# SCH_sensors_2026-05-06.net
KiCad netlist of a schematic drawn in EasyEDA
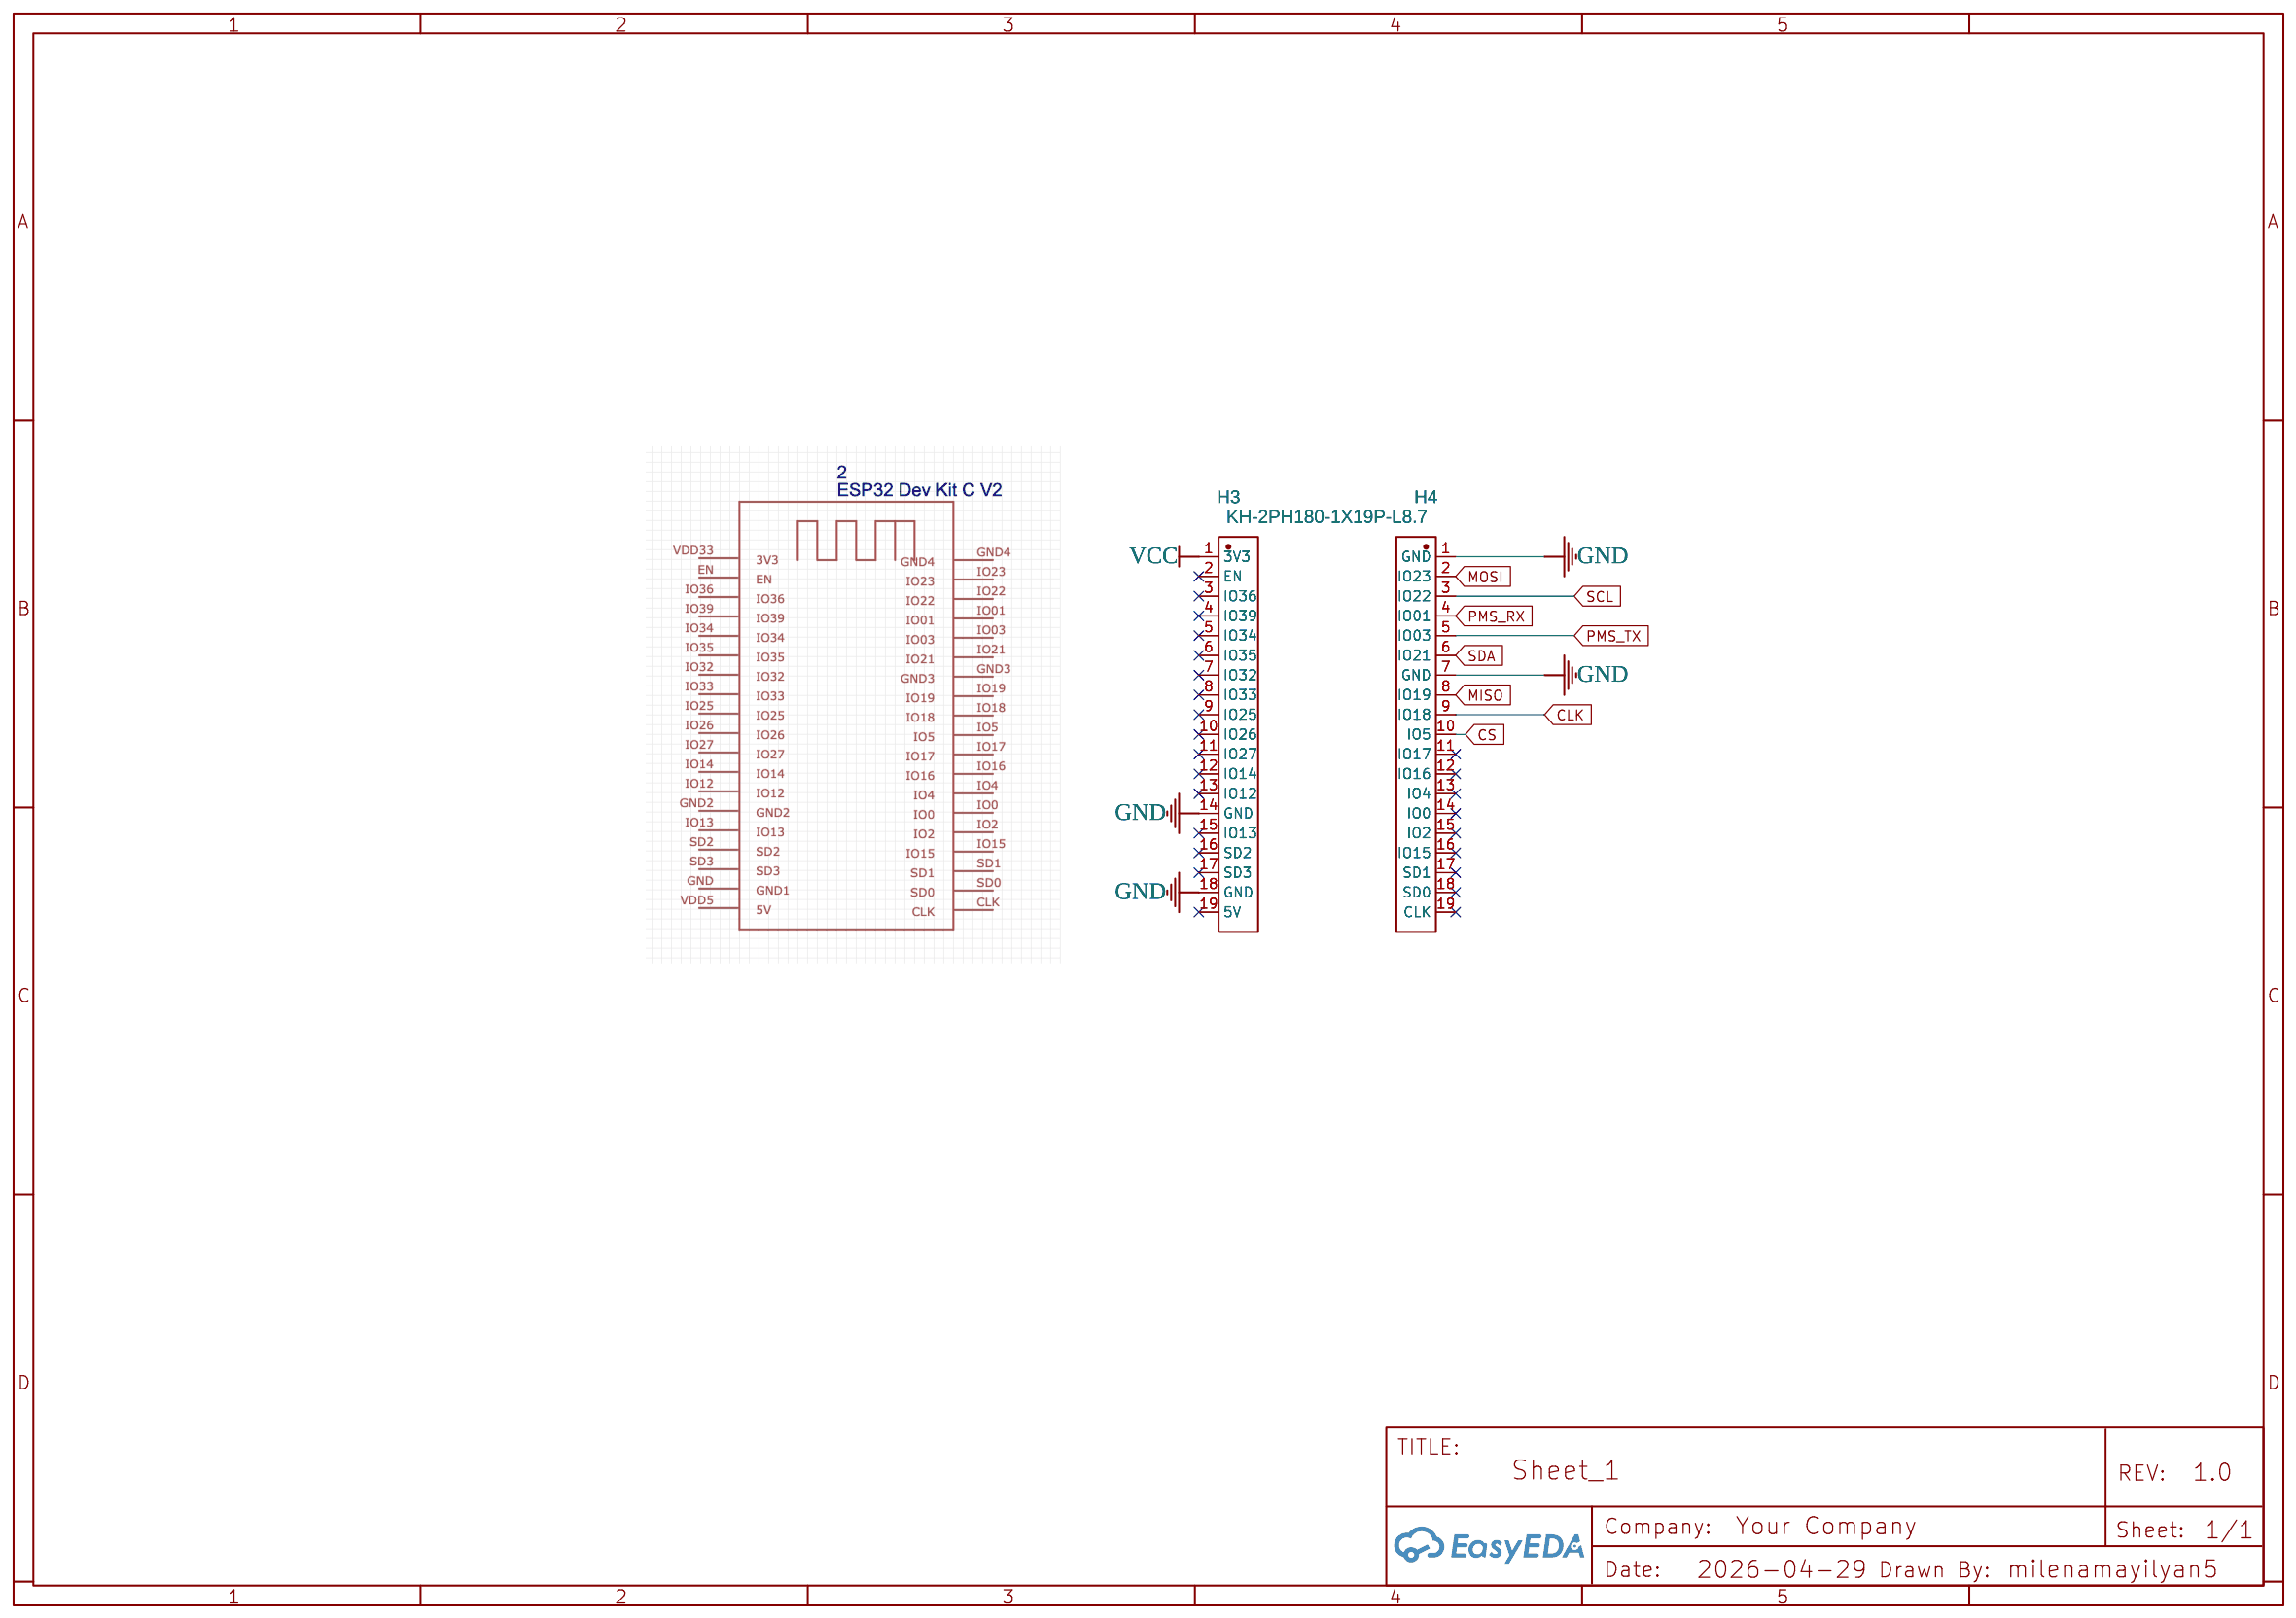
[diagram p0: esp32]
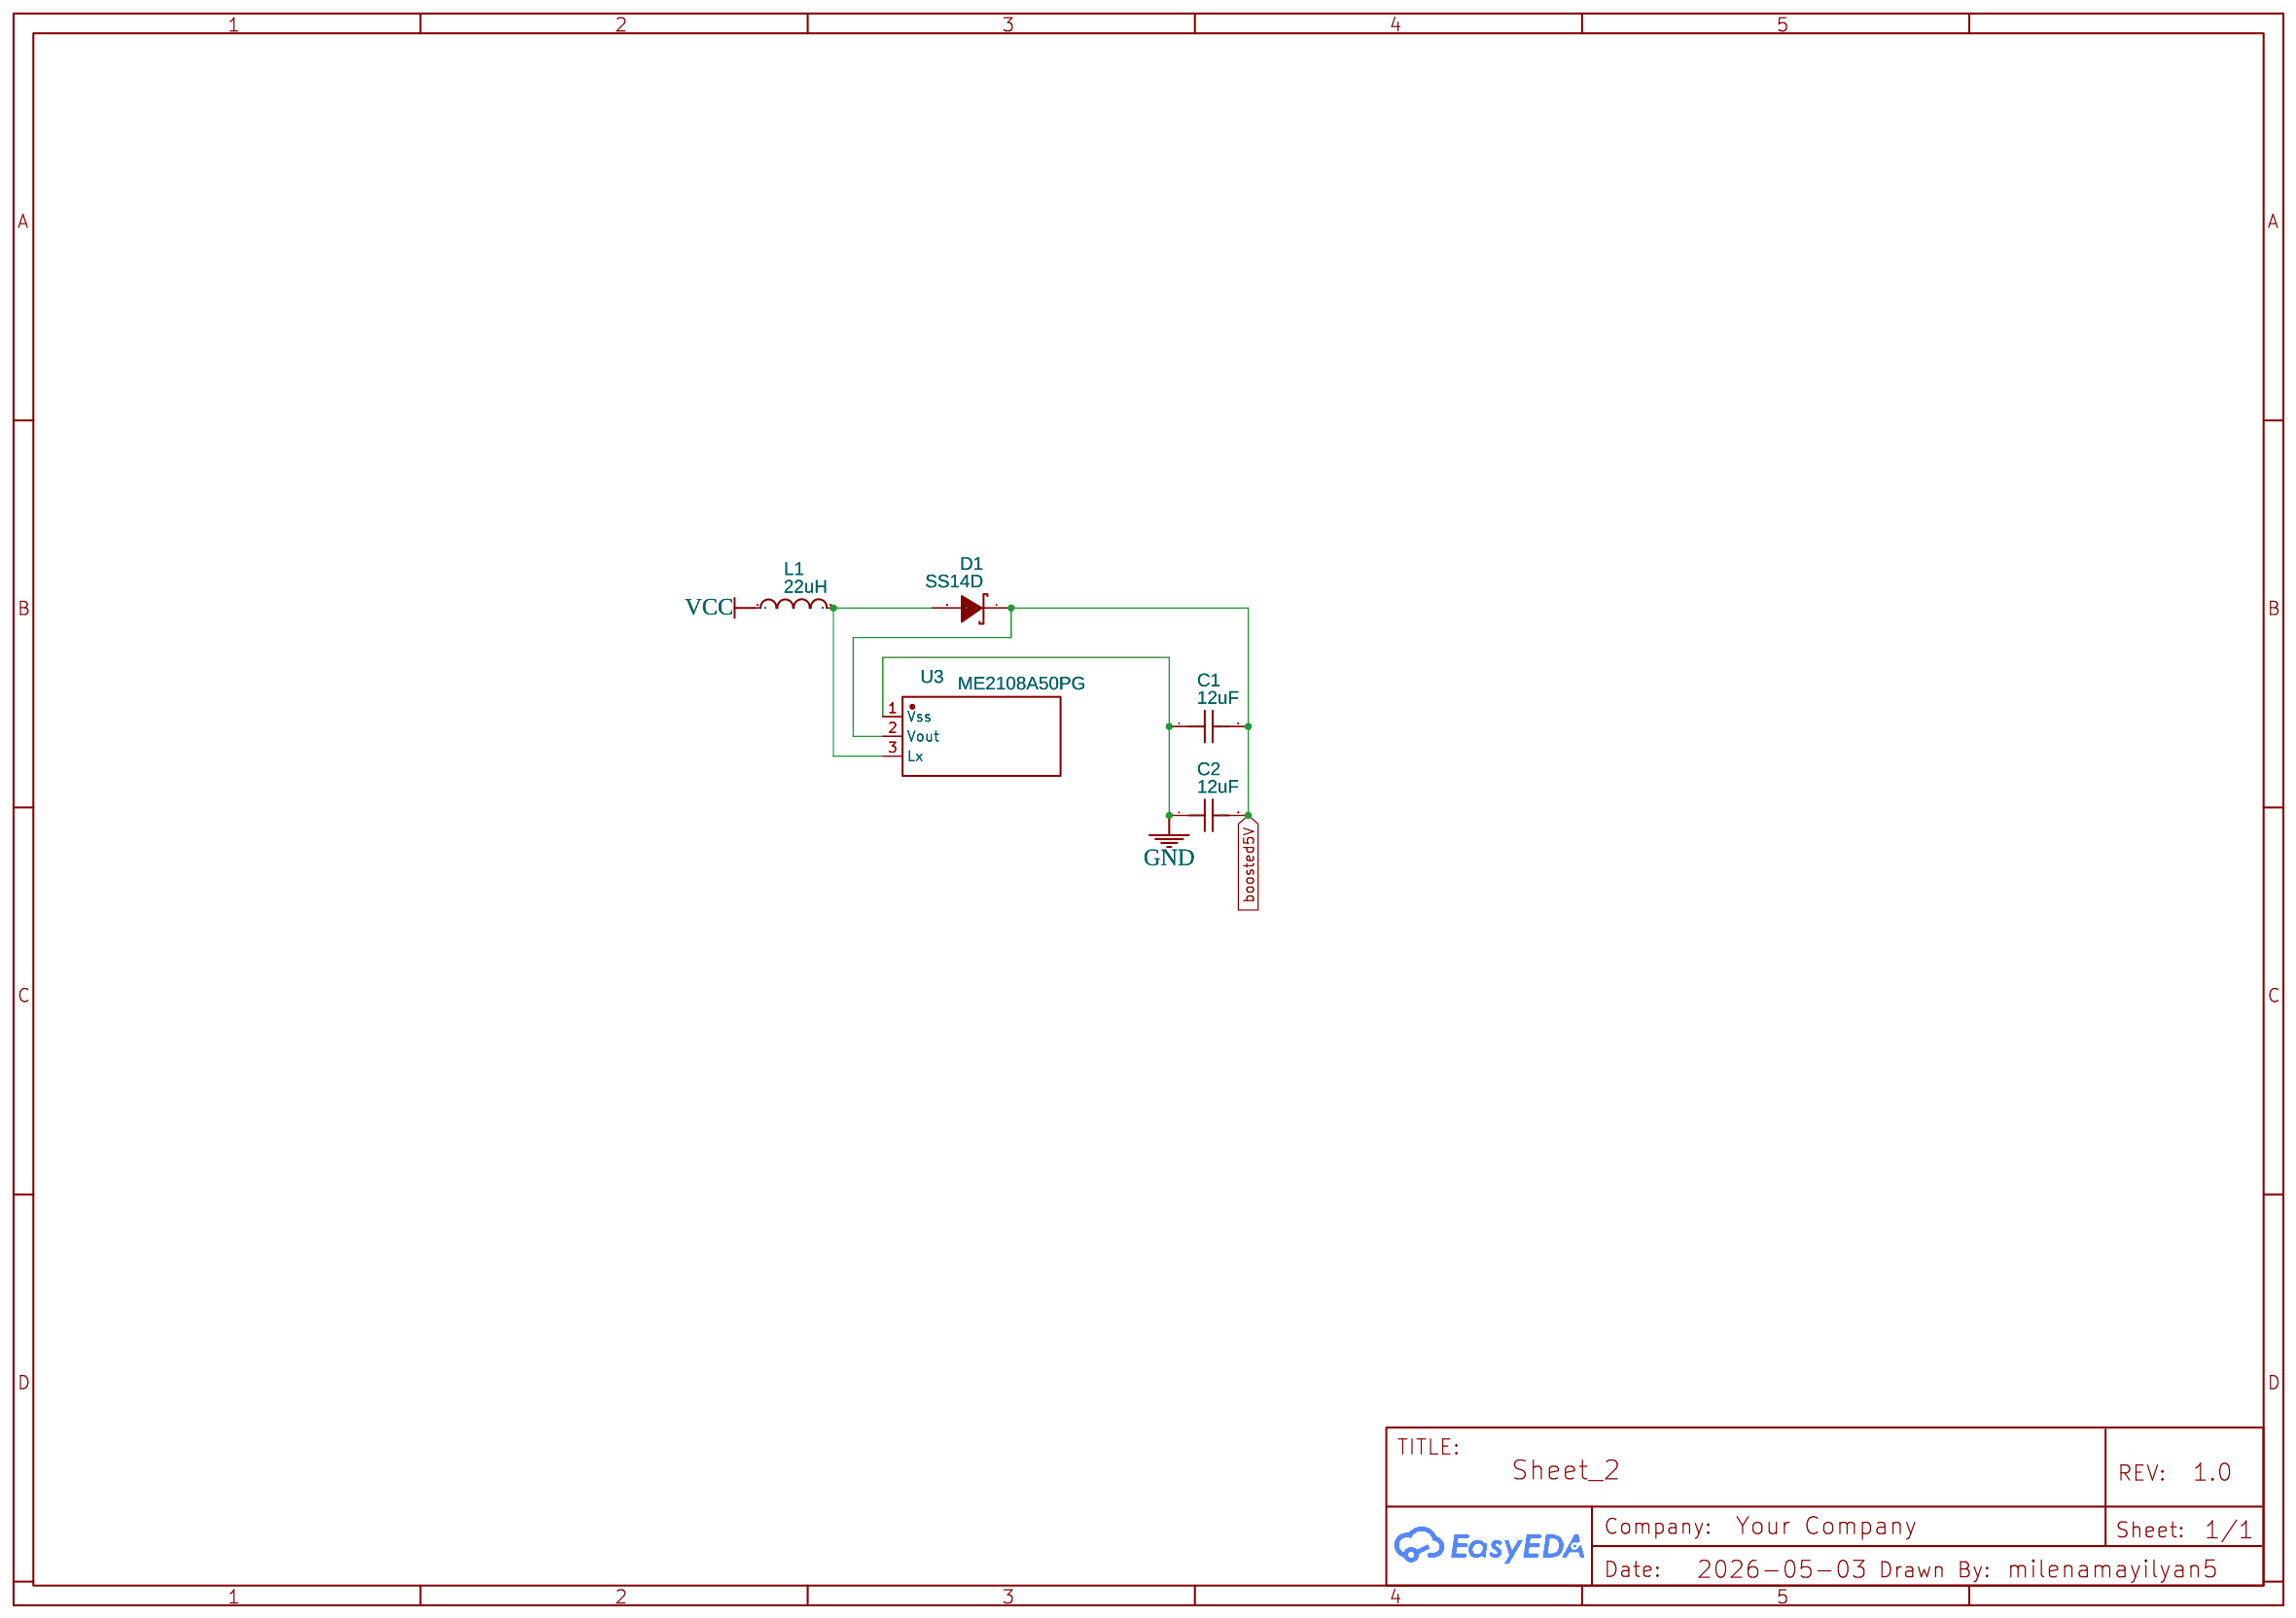
[diagram p1: booster]
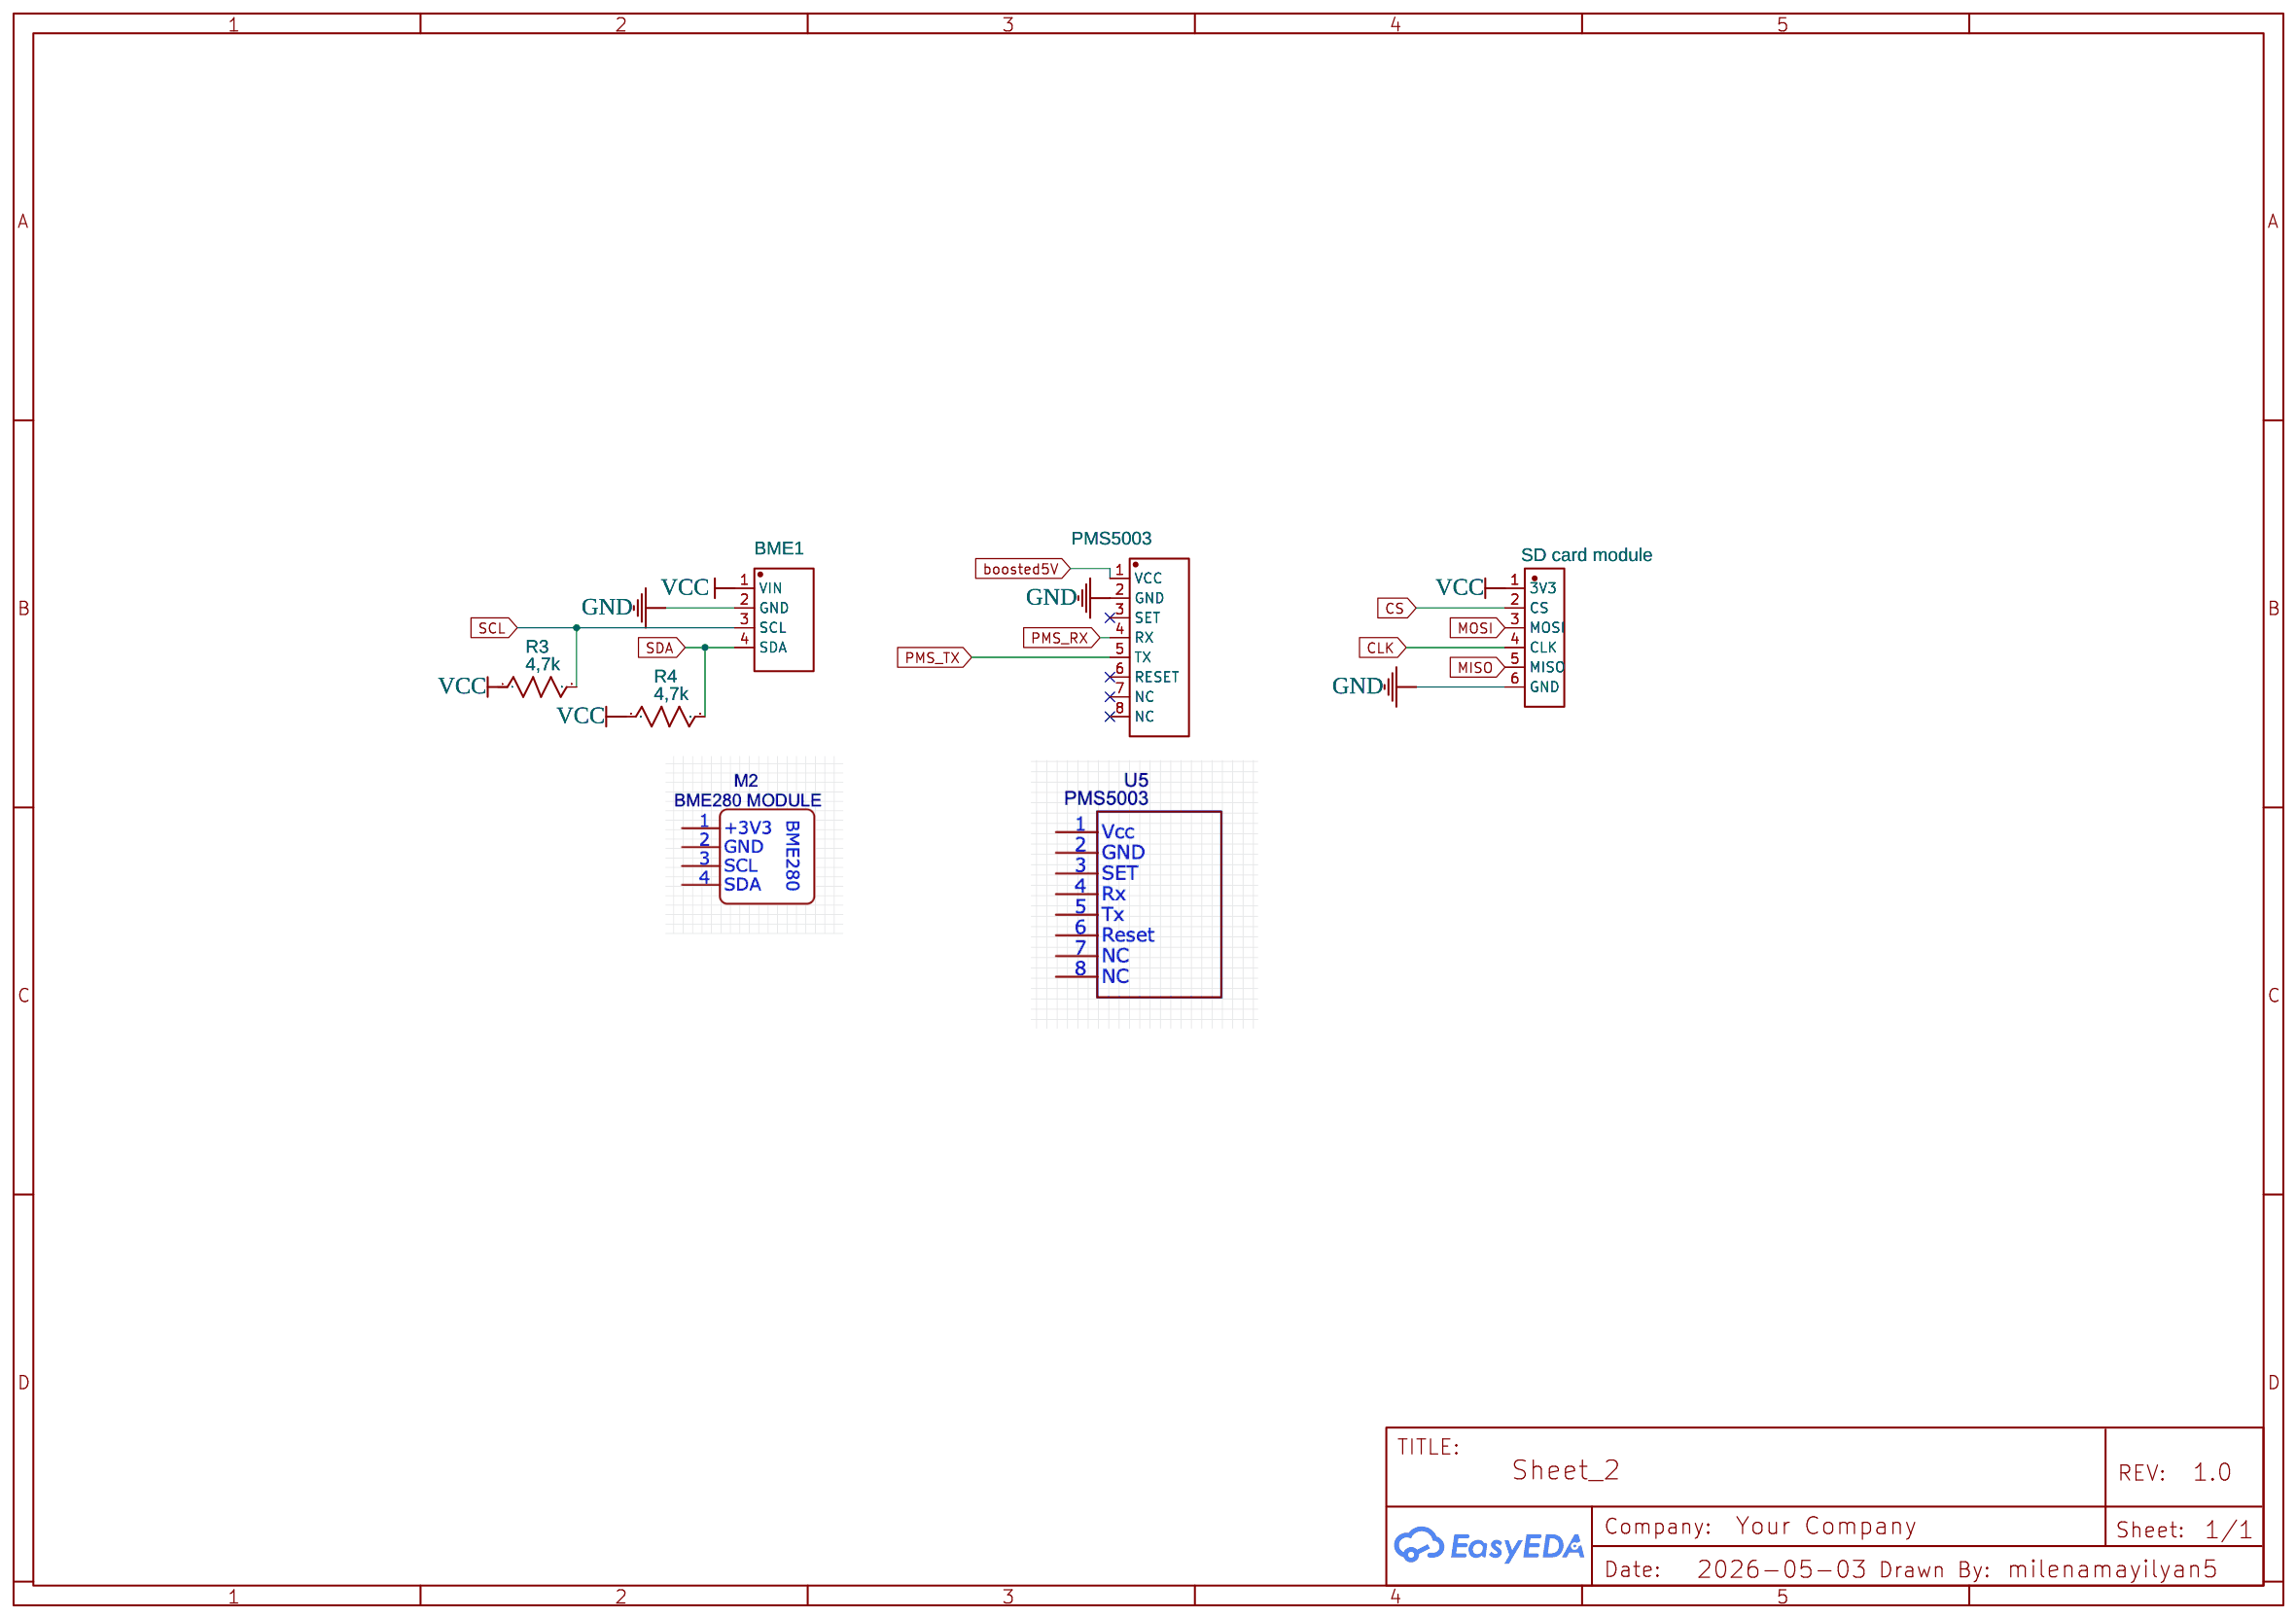
[diagram p2: sensors]

(export (version "E")
  (design (tool "Eeschema 10.0.6"))
  (components
    (comp (ref "H3")
      (value "KH-2PH180-1X19P-L8.7")
      (fields (field (name "Manufacturer") "kinghelm(金航标)"))
      (libsource (lib "") (part "KH-2PH180-1X19P-L8.7_1"))
    )
    (comp (ref "H4")
      (value "KH-2PH180-1X19P-L8.7")
      (fields (field (name "Manufacturer") "kinghelm(金航标)"))
      (libsource (lib "") (part "KH-2PH180-1X19P-L8.7"))
    )
    (comp (ref "C1") (value "12uF") (libsource (lib "") (part "C_0603_US")))
    (comp (ref "C2") (value "12uF") (libsource (lib "") (part "C_0603_US")))
    (comp (ref "D1")
      (value "SS14D")
      (fields (field (name "Manufacturer") "ST(先科)"))
      (libsource (lib "") (part "SS14D"))
    )
    (comp (ref "L1") (value "22uH") (libsource (lib "") (part "L0603_US")))
    (comp (ref "U3")
      (value "ME2108A50PG")
      (fields (field (name "Manufacturer") "MICRONE(南京微盟)"))
      (libsource (lib "") (part "ME2108A50PG"))
    )
    (comp (ref "BME1") (value "I2C RAIL COPY") (libsource (lib "") (part "I2C RAIL COPY")))
    (comp (ref "H1")
      (value "SD card module")
      (fields
        (field (name "Manufacturer Part") "HX PZ-2005WV-1x6P")
        (field (name "Manufacturer") "hanxia(韩下)")
      )
      (libsource (lib "") (part "HX PZ-2005WV-1X6P"))
    )
    (comp (ref "H6") (value "PMS5003") (libsource (lib "") (part "PIN HEADER 2.54 1X8 SCU")))
    (comp (ref "R3") (value "4,7k") (libsource (lib "") (part "R_0603_US")))
    (comp (ref "R4") (value "4,7k") (libsource (lib "") (part "R_0603_US")))
  )
  (nets
    (net (code "1") (name "CLK") (class "Default")
      (node (ref "H1") (pin "4") (pinfunction "CLK_4") (pintype "unspecified"))
      (node (ref "H4") (pin "9") (pinfunction "IO18_9") (pintype "unspecified"))
    )
    (net (code "2") (name "CS") (class "Default")
      (node (ref "H1") (pin "2") (pinfunction "CS_2") (pintype "unspecified"))
      (node (ref "H4") (pin "10") (pinfunction "IO5_10") (pintype "unspecified"))
    )
    (net (code "3") (name "GND") (class "Default")
      (node (ref "BME1") (pin "2") (pinfunction "GND_2") (pintype "unspecified"))
      (node (ref "C1") (pin "1") (pinfunction "1_1") (pintype "unspecified"))
      (node (ref "C2") (pin "1") (pinfunction "1_1") (pintype "unspecified"))
      (node (ref "H1") (pin "6") (pinfunction "GND_6") (pintype "unspecified"))
      (node (ref "H3") (pin "14") (pinfunction "GND_14") (pintype "unspecified"))
      (node (ref "H3") (pin "18") (pinfunction "GND_18") (pintype "unspecified"))
      (node (ref "H4") (pin "1") (pinfunction "GND_1") (pintype "unspecified"))
      (node (ref "H4") (pin "7") (pinfunction "GND_7") (pintype "unspecified"))
      (node (ref "H6") (pin "2") (pinfunction "GND_2") (pintype "unspecified"))
      (node (ref "U3") (pin "1") (pinfunction "Vss_1") (pintype "unspecified"))
    )
    (net (code "4") (name "MISO") (class "Default")
      (node (ref "H1") (pin "5") (pinfunction "MISO_5") (pintype "unspecified"))
      (node (ref "H4") (pin "8") (pinfunction "IO19_8") (pintype "unspecified"))
    )
    (net (code "5") (name "MOSI") (class "Default")
      (node (ref "H1") (pin "3") (pinfunction "MOSI_3") (pintype "unspecified"))
      (node (ref "H4") (pin "2") (pinfunction "IO23_2") (pintype "unspecified"))
    )
    (net (code "6") (name "Net-(D1-A)") (class "Default")
      (node (ref "D1") (pin "2") (pinfunction "A_2") (pintype "unspecified"))
      (node (ref "L1") (pin "2") (pinfunction "2_2") (pintype "unspecified"))
      (node (ref "U3") (pin "3") (pinfunction "Lx_3") (pintype "unspecified"))
    )
    (net (code "7") (name "PMS_RX") (class "Default")
      (node (ref "H4") (pin "4") (pinfunction "IO01_4") (pintype "unspecified"))
      (node (ref "H6") (pin "4") (pinfunction "RX_4") (pintype "unspecified"))
    )
    (net (code "8") (name "PMS_TX") (class "Default")
      (node (ref "H4") (pin "5") (pinfunction "IO03_5") (pintype "unspecified"))
      (node (ref "H6") (pin "5") (pinfunction "TX_5") (pintype "unspecified"))
    )
    (net (code "9") (name "SCL") (class "Default")
      (node (ref "BME1") (pin "3") (pinfunction "SCL_3") (pintype "unspecified"))
      (node (ref "H4") (pin "3") (pinfunction "IO22_3") (pintype "unspecified"))
      (node (ref "R3") (pin "2") (pinfunction "2_2") (pintype "unspecified"))
    )
    (net (code "10") (name "SDA") (class "Default")
      (node (ref "BME1") (pin "4") (pinfunction "SDA_4") (pintype "unspecified"))
      (node (ref "H4") (pin "6") (pinfunction "IO21_6") (pintype "unspecified"))
      (node (ref "R4") (pin "2") (pinfunction "2_2") (pintype "unspecified"))
    )
    (net (code "11") (name "VCC") (class "Default")
      (node (ref "BME1") (pin "1") (pinfunction "VIN_1") (pintype "unspecified"))
      (node (ref "H1") (pin "1") (pinfunction "3V3_1") (pintype "unspecified"))
      (node (ref "H3") (pin "1") (pinfunction "3V3_1") (pintype "unspecified"))
      (node (ref "L1") (pin "1") (pinfunction "1_1") (pintype "unspecified"))
      (node (ref "R3") (pin "1") (pinfunction "1_1") (pintype "unspecified"))
      (node (ref "R4") (pin "1") (pinfunction "1_1") (pintype "unspecified"))
    )
    (net (code "12") (name "boosted5V") (class "Default")
      (node (ref "C1") (pin "2") (pinfunction "2_2") (pintype "unspecified"))
      (node (ref "C2") (pin "2") (pinfunction "2_2") (pintype "unspecified"))
      (node (ref "D1") (pin "1") (pinfunction "K_1") (pintype "unspecified"))
      (node (ref "H6") (pin "1") (pinfunction "VCC_1") (pintype "unspecified"))
      (node (ref "U3") (pin "2") (pinfunction "Vout_2") (pintype "unspecified"))
    )
    (net (code "13") (name "unconnected-(H3-5V-Pad19)") (class "Default")
      (node (ref "H3") (pin "19") (pinfunction "5V_19") (pintype "unspecified+no_connect"))
    )
    (net (code "14") (name "unconnected-(H3-EN-Pad2)") (class "Default")
      (node (ref "H3") (pin "2") (pinfunction "EN_2") (pintype "unspecified+no_connect"))
    )
    (net (code "15") (name "unconnected-(H3-IO12-Pad13)") (class "Default")
      (node (ref "H3") (pin "13") (pinfunction "IO12_13") (pintype "unspecified+no_connect"))
    )
    (net (code "16") (name "unconnected-(H3-IO13-Pad15)") (class "Default")
      (node (ref "H3") (pin "15") (pinfunction "IO13_15") (pintype "unspecified+no_connect"))
    )
    (net (code "17") (name "unconnected-(H3-IO14-Pad12)") (class "Default")
      (node (ref "H3") (pin "12") (pinfunction "IO14_12") (pintype "unspecified+no_connect"))
    )
    (net (code "18") (name "unconnected-(H3-IO25-Pad9)") (class "Default")
      (node (ref "H3") (pin "9") (pinfunction "IO25_9") (pintype "unspecified+no_connect"))
    )
    (net (code "19") (name "unconnected-(H3-IO26-Pad10)") (class "Default")
      (node (ref "H3") (pin "10") (pinfunction "IO26_10") (pintype "unspecified+no_connect"))
    )
    (net (code "20") (name "unconnected-(H3-IO27-Pad11)") (class "Default")
      (node (ref "H3") (pin "11") (pinfunction "IO27_11") (pintype "unspecified+no_connect"))
    )
    (net (code "21") (name "unconnected-(H3-IO32-Pad7)") (class "Default")
      (node (ref "H3") (pin "7") (pinfunction "IO32_7") (pintype "unspecified+no_connect"))
    )
    (net (code "22") (name "unconnected-(H3-IO33-Pad8)") (class "Default")
      (node (ref "H3") (pin "8") (pinfunction "IO33_8") (pintype "unspecified+no_connect"))
    )
    (net (code "23") (name "unconnected-(H3-IO34-Pad5)") (class "Default")
      (node (ref "H3") (pin "5") (pinfunction "IO34_5") (pintype "unspecified+no_connect"))
    )
    (net (code "24") (name "unconnected-(H3-IO35-Pad6)") (class "Default")
      (node (ref "H3") (pin "6") (pinfunction "IO35_6") (pintype "unspecified+no_connect"))
    )
    (net (code "25") (name "unconnected-(H3-IO36-Pad3)") (class "Default")
      (node (ref "H3") (pin "3") (pinfunction "IO36_3") (pintype "unspecified+no_connect"))
    )
    (net (code "26") (name "unconnected-(H3-IO39-Pad4)") (class "Default")
      (node (ref "H3") (pin "4") (pinfunction "IO39_4") (pintype "unspecified+no_connect"))
    )
    (net (code "27") (name "unconnected-(H3-SD2-Pad16)") (class "Default")
      (node (ref "H3") (pin "16") (pinfunction "SD2_16") (pintype "unspecified+no_connect"))
    )
    (net (code "28") (name "unconnected-(H3-SD3-Pad17)") (class "Default")
      (node (ref "H3") (pin "17") (pinfunction "SD3_17") (pintype "unspecified+no_connect"))
    )
    (net (code "29") (name "unconnected-(H4-CLK-Pad19)") (class "Default")
      (node (ref "H4") (pin "19") (pinfunction "CLK_19") (pintype "unspecified+no_connect"))
    )
    (net (code "30") (name "unconnected-(H4-IO0-Pad14)") (class "Default")
      (node (ref "H4") (pin "14") (pinfunction "IO0_14") (pintype "unspecified+no_connect"))
    )
    (net (code "31") (name "unconnected-(H4-IO2-Pad15)") (class "Default")
      (node (ref "H4") (pin "15") (pinfunction "IO2_15") (pintype "unspecified+no_connect"))
    )
    (net (code "32") (name "unconnected-(H4-IO4-Pad13)") (class "Default")
      (node (ref "H4") (pin "13") (pinfunction "IO4_13") (pintype "unspecified+no_connect"))
    )
    (net (code "33") (name "unconnected-(H4-IO15-Pad16)") (class "Default")
      (node (ref "H4") (pin "16") (pinfunction "IO15_16") (pintype "unspecified+no_connect"))
    )
    (net (code "34") (name "unconnected-(H4-IO16-Pad12)") (class "Default")
      (node (ref "H4") (pin "12") (pinfunction "IO16_12") (pintype "unspecified+no_connect"))
    )
    (net (code "35") (name "unconnected-(H4-IO17-Pad11)") (class "Default")
      (node (ref "H4") (pin "11") (pinfunction "IO17_11") (pintype "unspecified+no_connect"))
    )
    (net (code "36") (name "unconnected-(H4-SD0-Pad18)") (class "Default")
      (node (ref "H4") (pin "18") (pinfunction "SD0_18") (pintype "unspecified+no_connect"))
    )
    (net (code "37") (name "unconnected-(H4-SD1-Pad17)") (class "Default")
      (node (ref "H4") (pin "17") (pinfunction "SD1_17") (pintype "unspecified+no_connect"))
    )
    (net (code "38") (name "unconnected-(H6-NC-Pad7)") (class "Default")
      (node (ref "H6") (pin "7") (pinfunction "NC_7") (pintype "unspecified+no_connect"))
    )
    (net (code "39") (name "unconnected-(H6-NC-Pad8)") (class "Default")
      (node (ref "H6") (pin "8") (pinfunction "NC_8") (pintype "unspecified+no_connect"))
    )
    (net (code "40") (name "unconnected-(H6-RESET-Pad6)") (class "Default")
      (node (ref "H6") (pin "6") (pinfunction "RESET_6") (pintype "unspecified+no_connect"))
    )
    (net (code "41") (name "unconnected-(H6-SET-Pad3)") (class "Default")
      (node (ref "H6") (pin "3") (pinfunction "SET_3") (pintype "unspecified+no_connect"))
    )
  )
)
